# Schematic_v14.net
KiCad netlist of a schematic drawn in EAGLE
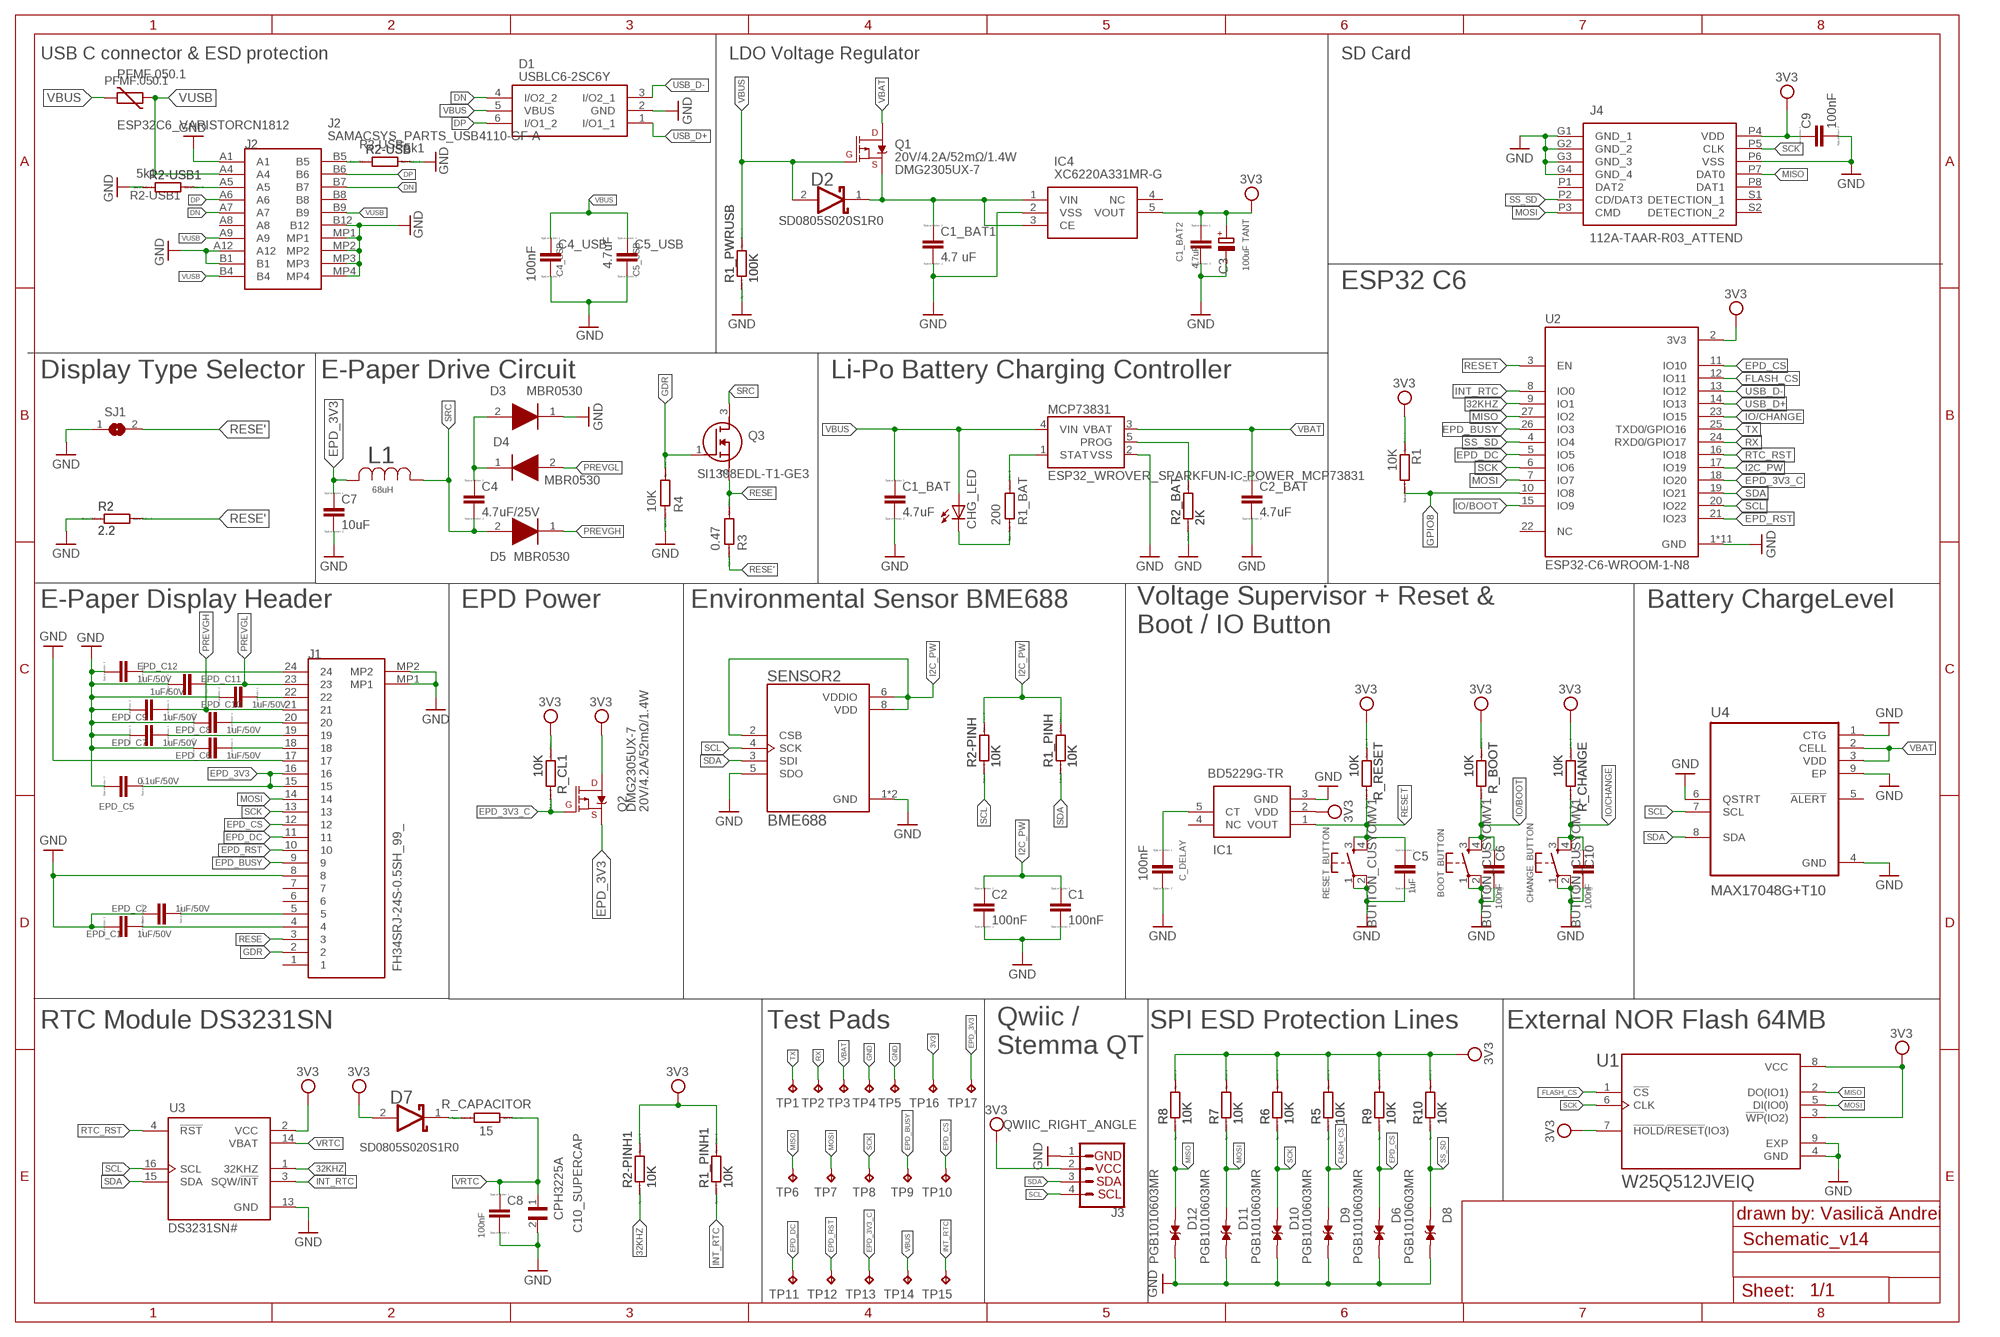
[diagram p0: schematic, sheet 1]

(export (version "E")
  (design (tool "Eeschema 10.0.6"))
  (components
    (comp (ref "BOOT_BUTTON")
      (value "BUTTON_CUSYOMV1")
      (footprint "eagle-import:MYBUTTON")
      (libsource (lib "eagle-import") (part "BUTTON_CUSYOMV1"))
    )
    (comp (ref "C1")
      (value "100nF")
      (footprint "eagle-import:ESP32_WROVER_EAGLE-LTSPICE_C0402")
      (libsource (lib "eagle-import") (part "ESP32_WROVER_EAGLE-LTSPICE_CC0402"))
    )
    (comp (ref "C1_BAT")
      (value "4.7uF")
      (footprint "eagle-import:ESP32_WROVER_EAGLE-LTSPICE_C0402")
      (libsource (lib "eagle-import") (part "ESP32_WROVER_EAGLE-LTSPICE_CC0402"))
    )
    (comp (ref "C1_BAT1")
      (value "4.7 uF")
      (footprint "eagle-import:EAGLE-LTSPICE_C0402")
      (fields (field (name "THERMALLOSS") "4.7 uF"))
      (libsource (lib "eagle-import") (part "EAGLE-LTSPICE_CC0402"))
    )
    (comp (ref "C1_BAT2")
      (value "4.7uF")
      (footprint "eagle-import:EAGLE-LTSPICE_C0402")
      (fields (field (name "SPICEPREFIX") "4.7uF"))
      (libsource (lib "eagle-import") (part "EAGLE-LTSPICE_CC0402"))
    )
    (comp (ref "C2")
      (value "100nF")
      (footprint "eagle-import:ESP32_WROVER_EAGLE-LTSPICE_C0402")
      (libsource (lib "eagle-import") (part "ESP32_WROVER_EAGLE-LTSPICE_CC0402"))
    )
    (comp (ref "C2_BAT")
      (value "4.7uF")
      (footprint "eagle-import:ESP32_WROVER_EAGLE-LTSPICE_C0402")
      (libsource (lib "eagle-import") (part "ESP32_WROVER_EAGLE-LTSPICE_CC0402"))
    )
    (comp (ref "C3")
      (value "100uF TANT")
      (footprint "eagle-import:RCL_CT3528")
      (fields (field (name "SPICEPREFIX") "100uF TANT"))
      (libsource (lib "eagle-import") (part "RCL_CPOL-EUCT3528"))
    )
    (comp (ref "C4")
      (value "4.7uF/25V")
      (footprint "eagle-import:ESP32_WROVER_EAGLE-LTSPICE_C0402")
      (libsource (lib "eagle-import") (part "ESP32_WROVER_EAGLE-LTSPICE_CC0402"))
    )
    (comp (ref "C4_USB")
      (value "100nF")
      (footprint "eagle-import:EAGLE-LTSPICE_C0402")
      (libsource (lib "eagle-import") (part "EAGLE-LTSPICE_CC0402"))
    )
    (comp (ref "C5")
      (value "1uF")
      (footprint "eagle-import:ESP32_WROVER_EAGLE-LTSPICE_C0402")
      (libsource (lib "eagle-import") (part "ESP32_WROVER_EAGLE-LTSPICE_CC0402"))
    )
    (comp (ref "C5_USB")
      (value "4.7uF")
      (footprint "eagle-import:EAGLE-LTSPICE_C0402")
      (libsource (lib "eagle-import") (part "EAGLE-LTSPICE_CC0402"))
    )
    (comp (ref "C6")
      (value "100nF")
      (footprint "eagle-import:ESP32_WROVER_EAGLE-LTSPICE_C0402")
      (libsource (lib "eagle-import") (part "ESP32_WROVER_EAGLE-LTSPICE_CC0402"))
    )
    (comp (ref "C7")
      (value "10uF")
      (footprint "eagle-import:ESP32_WROVER_EAGLE-LTSPICE_C0402")
      (libsource (lib "eagle-import") (part "ESP32_WROVER_EAGLE-LTSPICE_CC0402"))
    )
    (comp (ref "C8")
      (value "100nF")
      (footprint "eagle-import:ESP32_WROVER_EAGLE-LTSPICE_C0402")
      (libsource (lib "eagle-import") (part "ESP32_WROVER_EAGLE-LTSPICE_CC0402"))
    )
    (comp (ref "C9")
      (value "100nF")
      (footprint "eagle-import:EAGLE-LTSPICE_C0402")
      (fields (field (name "SPICEPREFIX") "100nF"))
      (libsource (lib "eagle-import") (part "EAGLE-LTSPICE_CC0402"))
    )
    (comp (ref "C10")
      (value "100nF")
      (footprint "eagle-import:ESP32_WROVER_EAGLE-LTSPICE_C0402")
      (libsource (lib "eagle-import") (part "ESP32_WROVER_EAGLE-LTSPICE_CC0402"))
    )
    (comp (ref "C10_SUPERCAP")
      (value "CPH3225A")
      (footprint "eagle-import:CAPCP3225X100N")
      (fields (field (name "MF") "Seiko Instruments"))
      (libsource (lib "eagle-import") (part "CPH3225A"))
    )
    (comp (ref "CHANGE_BUTTON")
      (value "BUTTON_CUSYOMV1")
      (footprint "eagle-import:MYBUTTON")
      (libsource (lib "eagle-import") (part "BUTTON_CUSYOMV1"))
    )
    (comp (ref "CHG_LED")
      (value "ADAFRUIT_LEDCHIP-LED0603")
      (footprint "eagle-import:ADAFRUIT_CHIP-LED0603")
      (libsource (lib "eagle-import") (part "ADAFRUIT_LEDCHIP-LED0603"))
    )
    (comp (ref "C_DELAY")
      (value "100nF")
      (footprint "eagle-import:ESP32_WROVER_EAGLE-LTSPICE_C0402")
      (libsource (lib "eagle-import") (part "ESP32_WROVER_EAGLE-LTSPICE_CC0402"))
    )
    (comp (ref "D1")
      (value "USBLC6-2SC6Y")
      (footprint "eagle-import:SOT95P280X145-6N")
      (fields (field (name "MF") "STMicroelectronics"))
      (libsource (lib "eagle-import") (part "USBLC6-2SC6Y"))
    )
    (comp (ref "D2")
      (value "ESP32_WROVER_AVX---SD0805S020S1R0_AVX_SD0805S020S1R0_0_0AVX_SD0805S020S1R0_0_0")
      (footprint "eagle-import:ESP32_WROVER_AVX---SD0805S020S1R0_AVX_SD0805S020S1R0_0")
      (fields
        (field (name "DIGIKEY_PART_NUMBER") "478-7800-1-ND")
        (field (name "MF") "AVX")
        (field (name "MOUSER_PART_NUMBER") "581-SD0805S020S1R0")
      )
      (libsource (lib "eagle-import") (part "ESP32_WROVER_AVX---SD0805S020S1R0_AVX_SD0805S020S1R0_0_0AVX_SD0805S020S1R0_0_0"))
    )
    (comp (ref "D3")
      (value "MBR0530")
      (footprint "eagle-import:SOD3716X135N")
      (fields (field (name "MF") "ON Semiconductor"))
      (libsource (lib "eagle-import") (part "MBR0530"))
    )
    (comp (ref "D4")
      (value "MBR0530")
      (footprint "eagle-import:SOD3716X135N")
      (fields (field (name "MF") "ON Semiconductor"))
      (libsource (lib "eagle-import") (part "MBR0530"))
    )
    (comp (ref "D5")
      (value "MBR0530")
      (footprint "eagle-import:SOD3716X135N")
      (fields (field (name "MF") "ON Semiconductor"))
      (libsource (lib "eagle-import") (part "MBR0530"))
    )
    (comp (ref "D6")
      (value "PGB1010603MR")
      (footprint "eagle-import:DIOC1608X36N")
      (fields (field (name "MF") "Littelfuse Inc."))
      (libsource (lib "eagle-import") (part "PGB1010603MR"))
    )
    (comp (ref "D7")
      (value "SD0805S020S1R0")
      (footprint "eagle-import:ESP32_WROVER_AVX---SD0805S020S1R0_AVX_SD0805S020S1R0_0")
      (fields
        (field (name "DIGIKEY_PART_NUMBER") "478-7800-1-ND")
        (field (name "MF") "AVX")
        (field (name "MOUSER_PART_NUMBER") "581-SD0805S020S1R0")
      )
      (libsource (lib "eagle-import") (part "ESP32_WROVER_AVX---SD0805S020S1R0_AVX_SD0805S020S1R0_0_0AVX_SD0805S020S1R0_0_0"))
    )
    (comp (ref "D8")
      (value "PGB1010603MR")
      (footprint "eagle-import:DIOC1608X36N")
      (fields (field (name "MF") "Littelfuse Inc."))
      (libsource (lib "eagle-import") (part "PGB1010603MR"))
    )
    (comp (ref "D9")
      (value "PGB1010603MR")
      (footprint "eagle-import:DIOC1608X36N")
      (fields (field (name "MF") "Littelfuse Inc."))
      (libsource (lib "eagle-import") (part "PGB1010603MR"))
    )
    (comp (ref "D10")
      (value "PGB1010603MR")
      (footprint "eagle-import:DIOC1608X36N")
      (fields (field (name "MF") "Littelfuse Inc."))
      (libsource (lib "eagle-import") (part "PGB1010603MR"))
    )
    (comp (ref "D11")
      (value "PGB1010603MR")
      (footprint "eagle-import:DIOC1608X36N")
      (fields (field (name "MF") "Littelfuse Inc."))
      (libsource (lib "eagle-import") (part "PGB1010603MR"))
    )
    (comp (ref "D12")
      (value "PGB1010603MR")
      (footprint "eagle-import:DIOC1608X36N")
      (fields (field (name "MF") "Littelfuse Inc."))
      (libsource (lib "eagle-import") (part "PGB1010603MR"))
    )
    (comp (ref "EPD_C1")
      (value "1uF/50V")
      (footprint "eagle-import:ESP32_WROVER_EAGLE-LTSPICE_C0402")
      (libsource (lib "eagle-import") (part "ESP32_WROVER_EAGLE-LTSPICE_CC0402"))
    )
    (comp (ref "EPD_C2")
      (value "1uF/50V")
      (footprint "eagle-import:ESP32_WROVER_EAGLE-LTSPICE_C0402")
      (libsource (lib "eagle-import") (part "ESP32_WROVER_EAGLE-LTSPICE_CC0402"))
    )
    (comp (ref "EPD_C5")
      (value "0.1uF/50V")
      (footprint "eagle-import:ESP32_WROVER_EAGLE-LTSPICE_C0402")
      (libsource (lib "eagle-import") (part "ESP32_WROVER_EAGLE-LTSPICE_CC0402"))
    )
    (comp (ref "EPD_C6")
      (value "1uF/50V")
      (footprint "eagle-import:ESP32_WROVER_EAGLE-LTSPICE_C0402")
      (libsource (lib "eagle-import") (part "ESP32_WROVER_EAGLE-LTSPICE_CC0402"))
    )
    (comp (ref "EPD_C7")
      (value "1uF/50V")
      (footprint "eagle-import:ESP32_WROVER_EAGLE-LTSPICE_C0402")
      (libsource (lib "eagle-import") (part "ESP32_WROVER_EAGLE-LTSPICE_CC0402"))
    )
    (comp (ref "EPD_C8")
      (value "1uF/50V")
      (footprint "eagle-import:ESP32_WROVER_EAGLE-LTSPICE_C0402")
      (libsource (lib "eagle-import") (part "ESP32_WROVER_EAGLE-LTSPICE_CC0402"))
    )
    (comp (ref "EPD_C9")
      (value "1uF/50V")
      (footprint "eagle-import:ESP32_WROVER_EAGLE-LTSPICE_C0402")
      (libsource (lib "eagle-import") (part "ESP32_WROVER_EAGLE-LTSPICE_CC0402"))
    )
    (comp (ref "EPD_C10")
      (value "1uF/50V")
      (footprint "eagle-import:ESP32_WROVER_EAGLE-LTSPICE_C0402")
      (libsource (lib "eagle-import") (part "ESP32_WROVER_EAGLE-LTSPICE_CC0402"))
    )
    (comp (ref "EPD_C11")
      (value "1uF/50V")
      (footprint "eagle-import:ESP32_WROVER_EAGLE-LTSPICE_C0402")
      (libsource (lib "eagle-import") (part "ESP32_WROVER_EAGLE-LTSPICE_CC0402"))
    )
    (comp (ref "EPD_C12")
      (value "1uF/50V")
      (footprint "eagle-import:ESP32_WROVER_EAGLE-LTSPICE_C0402")
      (libsource (lib "eagle-import") (part "ESP32_WROVER_EAGLE-LTSPICE_CC0402"))
    )
    (comp (ref "IC1")
      (value "BD5229G-TR")
      (footprint "eagle-import:SOT95P280X125-5N")
      (fields (field (name "MOUSER_PART_NUMBER") "755-BD5229G-TR"))
      (libsource (lib "eagle-import") (part "BD5229G-TR"))
    )
    (comp (ref "IC4")
      (value "XC6220A331MR-G")
      (footprint "eagle-import:SOT95P280X120-5N")
      (fields (field (name "MOUSER_PART_NUMBER") "865-XC6220A331MR-G"))
      (libsource (lib "eagle-import") (part "XC6220A331MR-G"))
    )
    (comp (ref "J1")
      (value "FH34SRJ-24S-0.5SH_99_")
      (footprint "eagle-import:FH34SRJ24S05SH99")
      (fields
        (field (name "MANUFACTURER_PART_NUMBER") "FH34SRJ-24S-0.5SH(99)")
        (field (name "MOUSER_PART_NUMBER") "798-FH34SRJ24S05SH99")
      )
      (libsource (lib "eagle-import") (part "FH34SRJ-24S-0.5SH_99_"))
    )
    (comp (ref "J2")
      (value "SAMACSYS_PARTS_USB4110-GF-A")
      (footprint "eagle-import:SAMACSYS_PARTS_USB4110GFA")
      (fields
        (field (name "MANUFACTURER_PART_NUMBER") "USB4110-GF-A")
        (field (name "MOUSER_PART_NUMBER") "640-USB4110-GF-A")
      )
      (libsource (lib "eagle-import") (part "SAMACSYS_PARTS_USB4110-GF-A"))
    )
    (comp (ref "J3")
      (value "QWIIC_RIGHT_ANGLE")
      (footprint "eagle-import:JST04_1MM_RA")
      (libsource (lib "eagle-import") (part "QWIIC_CONNECTORJS-1MM"))
    )
    (comp (ref "J4")
      (value "112A-TAAR-R03_ATTEND")
      (footprint "eagle-import:112ATAARR03ATTEND")
      (fields (field (name "MANUFACTURER_PART_NUMBER") "112A-TAAR-R03 ATTEND"))
      (libsource (lib "eagle-import") (part "112A-TAAR-R03_ATTEND"))
    )
    (comp (ref "L1")
      (value "744043680IND_4828-WE-TPC_WRE")
      (footprint "eagle-import:IND_4828-WE-TPC_WRE")
      (fields
        (field (name "MANUFACTURER_PART_NUMBER") "744043680")
        (field (name "MANUFACTURER_PART_NUMBER_1") "68uH")
        (field (name "COPYRIGHT") "Copyright (C) 2024 Ultra Librarian. All rights reserved.")
      )
      (libsource (lib "eagle-import") (part "744043680IND_4828-WE-TPC_WRE"))
    )
    (comp (ref "MCP73831")
      (value "ESP32_WROVER_SPARKFUN-IC-POWER_MCP73831")
      (footprint "eagle-import:ESP32_WROVER_SPARKFUN-IC-POWER_SOT23-5")
      (libsource (lib "eagle-import") (part "ESP32_WROVER_SPARKFUN-IC-POWER_MCP73831"))
    )
    (comp (ref "PFMF.050.1")
      (value "ESP32C6_VARISTORCN1812")
      (footprint "eagle-import:ESP32C6_VARISTOR_CT_CN1812")
      (libsource (lib "eagle-import") (part "ESP32C6_VARISTORCN1812"))
    )
    (comp (ref "Q1")
      (value "20V/4.2A/52mΩ/1.4W")
      (footprint "eagle-import:ESP32_WROVER_SPARKFUN-DISCRETESEMI_SOT23-3")
      (libsource (lib "eagle-import") (part "ESP32_WROVER_SPARKFUN-DISCRETESEMI_MOSFET_PCH-DMG2305UX-7"))
    )
    (comp (ref "Q2")
      (value "20V/4.2A/52mΩ/1.4W")
      (footprint "eagle-import:ESP32_WROVER_SPARKFUN-DISCRETESEMI_SOT23-3")
      (libsource (lib "eagle-import") (part "ESP32_WROVER_SPARKFUN-DISCRETESEMI_MOSFET_PCH-DMG2305UX-7"))
    )
    (comp (ref "Q3")
      (value "SI1308EDL-T1-GE3")
      (footprint "eagle-import:SOT65P210X110-3N")
      (fields (field (name "MF") "Vishay Siliconix"))
      (libsource (lib "eagle-import") (part "SI1308EDL-T1-GE3"))
    )
    (comp (ref "R1")
      (value "10K")
      (footprint "eagle-import:ESP32_WROVER_EAGLE-LTSPICE_R0402")
      (libsource (lib "eagle-import") (part "ESP32_WROVER_EAGLE-LTSPICE_RR0402"))
    )
    (comp (ref "R1_BAT")
      (value "200")
      (footprint "eagle-import:ESP32_WROVER_EAGLE-LTSPICE_R0402")
      (libsource (lib "eagle-import") (part "ESP32_WROVER_EAGLE-LTSPICE_RR0402"))
    )
    (comp (ref "R1_PINH")
      (value "10K")
      (footprint "eagle-import:ESP32_WROVER_EAGLE-LTSPICE_R0402")
      (libsource (lib "eagle-import") (part "ESP32_WROVER_EAGLE-LTSPICE_RR0402"))
    )
    (comp (ref "R1_PINH1")
      (value "10K")
      (footprint "eagle-import:ESP32_WROVER_EAGLE-LTSPICE_R0402")
      (libsource (lib "eagle-import") (part "ESP32_WROVER_EAGLE-LTSPICE_RR0402"))
    )
    (comp (ref "R1_PWRUSB")
      (value "100K")
      (footprint "eagle-import:ESP32_WROVER_EAGLE-LTSPICE_R0402")
      (fields (field (name "SPICEMODEL") "100K"))
      (libsource (lib "eagle-import") (part "ESP32_WROVER_EAGLE-LTSPICE_RR0402"))
    )
    (comp (ref "R2")
      (value "2.2")
      (footprint "eagle-import:ESP32_WROVER_EAGLE-LTSPICE_R0402")
      (fields (field (name "SPICEMODEL") "2.2"))
      (libsource (lib "eagle-import") (part "ESP32_WROVER_EAGLE-LTSPICE_RR0402"))
    )
    (comp (ref "R2-PINH")
      (value "10K")
      (footprint "eagle-import:ESP32_WROVER_EAGLE-LTSPICE_R0402")
      (libsource (lib "eagle-import") (part "ESP32_WROVER_EAGLE-LTSPICE_RR0402"))
    )
    (comp (ref "R2-PINH1")
      (value "10K")
      (footprint "eagle-import:ESP32_WROVER_EAGLE-LTSPICE_R0402")
      (libsource (lib "eagle-import") (part "ESP32_WROVER_EAGLE-LTSPICE_RR0402"))
    )
    (comp (ref "R2-USB")
      (value "5k1")
      (footprint "eagle-import:ESP32_WROVER_EAGLE-LTSPICE_R0402")
      (libsource (lib "eagle-import") (part "ESP32_WROVER_EAGLE-LTSPICE_RR0402"))
    )
    (comp (ref "R2-USB1")
      (value "5k1")
      (footprint "eagle-import:ESP32_WROVER_EAGLE-LTSPICE_R0402")
      (libsource (lib "eagle-import") (part "ESP32_WROVER_EAGLE-LTSPICE_RR0402"))
    )
    (comp (ref "R2_BAT")
      (value "2K")
      (footprint "eagle-import:ESP32_WROVER_EAGLE-LTSPICE_R0402")
      (libsource (lib "eagle-import") (part "ESP32_WROVER_EAGLE-LTSPICE_RR0402"))
    )
    (comp (ref "R3")
      (value "0.47")
      (footprint "eagle-import:ESP32_WROVER_EAGLE-LTSPICE_R0402")
      (libsource (lib "eagle-import") (part "ESP32_WROVER_EAGLE-LTSPICE_RR0402"))
    )
    (comp (ref "R4")
      (value "10K")
      (footprint "eagle-import:ESP32_WROVER_EAGLE-LTSPICE_R0402")
      (libsource (lib "eagle-import") (part "ESP32_WROVER_EAGLE-LTSPICE_RR0402"))
    )
    (comp (ref "R5")
      (value "10K")
      (footprint "eagle-import:ESP32_WROVER_EAGLE-LTSPICE_R0402")
      (libsource (lib "eagle-import") (part "ESP32_WROVER_EAGLE-LTSPICE_RR0402"))
    )
    (comp (ref "R6")
      (value "10K")
      (footprint "eagle-import:ESP32_WROVER_EAGLE-LTSPICE_R0402")
      (libsource (lib "eagle-import") (part "ESP32_WROVER_EAGLE-LTSPICE_RR0402"))
    )
    (comp (ref "R7")
      (value "10K")
      (footprint "eagle-import:ESP32_WROVER_EAGLE-LTSPICE_R0402")
      (libsource (lib "eagle-import") (part "ESP32_WROVER_EAGLE-LTSPICE_RR0402"))
    )
    (comp (ref "R8")
      (value "10K")
      (footprint "eagle-import:ESP32_WROVER_EAGLE-LTSPICE_R0402")
      (libsource (lib "eagle-import") (part "ESP32_WROVER_EAGLE-LTSPICE_RR0402"))
    )
    (comp (ref "R9")
      (value "10K")
      (footprint "eagle-import:ESP32_WROVER_EAGLE-LTSPICE_R0402")
      (libsource (lib "eagle-import") (part "ESP32_WROVER_EAGLE-LTSPICE_RR0402"))
    )
    (comp (ref "R10")
      (value "10K")
      (footprint "eagle-import:ESP32_WROVER_EAGLE-LTSPICE_R0402")
      (libsource (lib "eagle-import") (part "ESP32_WROVER_EAGLE-LTSPICE_RR0402"))
    )
    (comp (ref "RESET_BUTTON")
      (value "BUTTON_CUSYOMV1")
      (footprint "eagle-import:MYBUTTON")
      (libsource (lib "eagle-import") (part "BUTTON_CUSYOMV1"))
    )
    (comp (ref "R_BOOT")
      (value "10K")
      (footprint "eagle-import:ESP32_WROVER_EAGLE-LTSPICE_R0402")
      (libsource (lib "eagle-import") (part "ESP32_WROVER_EAGLE-LTSPICE_RR0402"))
    )
    (comp (ref "R_CAPACITOR")
      (value "15")
      (footprint "eagle-import:ESP32_WROVER_EAGLE-LTSPICE_R0402")
      (libsource (lib "eagle-import") (part "ESP32_WROVER_EAGLE-LTSPICE_RR0402"))
    )
    (comp (ref "R_CHANGE")
      (value "10K")
      (footprint "eagle-import:ESP32_WROVER_EAGLE-LTSPICE_R0402")
      (libsource (lib "eagle-import") (part "ESP32_WROVER_EAGLE-LTSPICE_RR0402"))
    )
    (comp (ref "R_CL1")
      (value "10K")
      (footprint "eagle-import:ESP32_WROVER_EAGLE-LTSPICE_R0402")
      (libsource (lib "eagle-import") (part "ESP32_WROVER_EAGLE-LTSPICE_RR0402"))
    )
    (comp (ref "R_RESET")
      (value "10K")
      (footprint "eagle-import:ESP32_WROVER_EAGLE-LTSPICE_R0402")
      (libsource (lib "eagle-import") (part "ESP32_WROVER_EAGLE-LTSPICE_RR0402"))
    )
    (comp (ref "SENSOR2")
      (value "BME688")
      (footprint "eagle-import:ESP32_WROVER_BME680_PSON80P300X300X100-8N")
      (fields (field (name "MF") "Bosch Sensortec") (field (name "MP") "BME680"))
      (libsource (lib "eagle-import") (part "ESP32_WROVER_BME680_BME680"))
    )
    (comp (ref "SJ1") (value "SJ") (footprint "eagle-import:SJ") (libsource (lib "eagle-import") (part "SJ")))
    (comp (ref "TP1")
      (value "TPTP20R")
      (footprint "eagle-import:TP20R")
      (libsource (lib "eagle-import") (part "TPTP20R"))
    )
    (comp (ref "TP2")
      (value "TPTP20R")
      (footprint "eagle-import:TP20R")
      (libsource (lib "eagle-import") (part "TPTP20R"))
    )
    (comp (ref "TP3")
      (value "TPTP20R")
      (footprint "eagle-import:TP20R")
      (libsource (lib "eagle-import") (part "TPTP20R"))
    )
    (comp (ref "TP4")
      (value "TPTP20R")
      (footprint "eagle-import:TP20R")
      (libsource (lib "eagle-import") (part "TPTP20R"))
    )
    (comp (ref "TP5")
      (value "TPTP20R")
      (footprint "eagle-import:TP20R")
      (libsource (lib "eagle-import") (part "TPTP20R"))
    )
    (comp (ref "TP6")
      (value "TPTP20R")
      (footprint "eagle-import:TP20R")
      (libsource (lib "eagle-import") (part "TPTP20R"))
    )
    (comp (ref "TP7")
      (value "TPTP20R")
      (footprint "eagle-import:TP20R")
      (libsource (lib "eagle-import") (part "TPTP20R"))
    )
    (comp (ref "TP8")
      (value "TPTP20R")
      (footprint "eagle-import:TP20R")
      (libsource (lib "eagle-import") (part "TPTP20R"))
    )
    (comp (ref "TP9")
      (value "TPTP20R")
      (footprint "eagle-import:TP20R")
      (libsource (lib "eagle-import") (part "TPTP20R"))
    )
    (comp (ref "TP10")
      (value "TPTP20R")
      (footprint "eagle-import:TP20R")
      (libsource (lib "eagle-import") (part "TPTP20R"))
    )
    (comp (ref "TP11")
      (value "TPTP20R")
      (footprint "eagle-import:TP20R")
      (libsource (lib "eagle-import") (part "TPTP20R"))
    )
    (comp (ref "TP12")
      (value "TPTP20R")
      (footprint "eagle-import:TP20R")
      (libsource (lib "eagle-import") (part "TPTP20R"))
    )
    (comp (ref "TP13")
      (value "TPTP20R")
      (footprint "eagle-import:TP20R")
      (libsource (lib "eagle-import") (part "TPTP20R"))
    )
    (comp (ref "TP14")
      (value "TPTP20R")
      (footprint "eagle-import:TP20R")
      (libsource (lib "eagle-import") (part "TPTP20R"))
    )
    (comp (ref "TP15")
      (value "TPTP20R")
      (footprint "eagle-import:TP20R")
      (libsource (lib "eagle-import") (part "TPTP20R"))
    )
    (comp (ref "TP16")
      (value "TPTP20R")
      (footprint "eagle-import:TP20R")
      (libsource (lib "eagle-import") (part "TPTP20R"))
    )
    (comp (ref "TP17")
      (value "TPTP20R")
      (footprint "eagle-import:TP20R")
      (libsource (lib "eagle-import") (part "TPTP20R"))
    )
    (comp (ref "U1")
      (value "W25Q512JVEIQ")
      (footprint "eagle-import:SON127P600X800X80-9N")
      (fields (field (name "MF") "Winbond Electronics"))
      (libsource (lib "eagle-import") (part "W25Q512JVEIQ"))
    )
    (comp (ref "U2")
      (value "ESP32-C6-WROOM-1-N8")
      (footprint "eagle-import:XCVR_ESP32-C6-WROOM-1-N8")
      (fields (field (name "MF") "Espressif Systems"))
      (libsource (lib "eagle-import") (part "ESP32-C6-WROOM-1-N8"))
    )
    (comp (ref "U3")
      (value "DS3231SN#")
      (footprint "eagle-import:SOIC127P1032X265-16N")
      (fields (field (name "MF") "Analog Devices"))
      (libsource (lib "eagle-import") (part "DS3231SN#"))
    )
    (comp (ref "U4")
      (value "MAX17048G+T10")
      (footprint "eagle-import:SON50P200X200X80-9N")
      (fields (field (name "MF") "Analog Devices"))
      (libsource (lib "eagle-import") (part "MAX17048G+T10"))
    )
  )
  (nets
    (net (code "1") (name "3V3") (class "Default")
      (node (ref "C1_BAT2") (pin "1") (pinfunction "1_1") (pintype "passive"))
      (node (ref "C3") (pin "+") (pinfunction "+_+") (pintype "passive"))
      (node (ref "C9") (pin "1") (pinfunction "1_1") (pintype "passive"))
      (node (ref "D7") (pin "2") (pinfunction "ANODE_2") (pintype "bidirectional"))
      (node (ref "IC1") (pin "2") (pinfunction "VDD_2") (pintype "bidirectional"))
      (node (ref "IC4") (pin "5") (pinfunction "VOUT_5") (pintype "bidirectional"))
      (node (ref "J3") (pin "2") (pinfunction "2_2") (pintype "power_in"))
      (node (ref "J4") (pin "P4") (pinfunction "VDD_P4") (pintype "bidirectional"))
      (node (ref "Q2") (pin "3") (pinfunction "D_3") (pintype "bidirectional"))
      (node (ref "R1") (pin "1") (pinfunction "1_1") (pintype "passive"))
      (node (ref "R10") (pin "2") (pinfunction "2_2") (pintype "passive"))
      (node (ref "R1_PINH1") (pin "2") (pinfunction "2_2") (pintype "passive"))
      (node (ref "R2-PINH1") (pin "2") (pinfunction "2_2") (pintype "passive"))
      (node (ref "R5") (pin "2") (pinfunction "2_2") (pintype "passive"))
      (node (ref "R6") (pin "2") (pinfunction "2_2") (pintype "passive"))
      (node (ref "R7") (pin "2") (pinfunction "2_2") (pintype "passive"))
      (node (ref "R8") (pin "2") (pinfunction "2_2") (pintype "passive"))
      (node (ref "R9") (pin "2") (pinfunction "2_2") (pintype "passive"))
      (node (ref "R_BOOT") (pin "1") (pinfunction "1_1") (pintype "passive"))
      (node (ref "R_CHANGE") (pin "1") (pinfunction "1_1") (pintype "passive"))
      (node (ref "R_CL1") (pin "1") (pinfunction "1_1") (pintype "passive"))
      (node (ref "R_RESET") (pin "1") (pinfunction "1_1") (pintype "passive"))
      (node (ref "TP16") (pin "TP") (pinfunction "TP_TP") (pintype "input"))
      (node (ref "U1") (pin "3") (pinfunction "~{WP}(IO2)_3") (pintype "bidirectional"))
      (node (ref "U1") (pin "7") (pinfunction "~{HOLD}/~{RESET}(IO3)_7") (pintype "bidirectional"))
      (node (ref "U1") (pin "8") (pinfunction "VCC_8") (pintype "power_in"))
      (node (ref "U2") (pin "2") (pinfunction "3V3_2") (pintype "power_in"))
      (node (ref "U3") (pin "2") (pinfunction "VCC_2") (pintype "power_in"))
    )
    (net (code "2") (name "32KHZ") (class "Default")
      (node (ref "R2-PINH1") (pin "1") (pinfunction "1_1") (pintype "passive"))
      (node (ref "U2") (pin "9") (pinfunction "IO1_9") (pintype "bidirectional"))
      (node (ref "U3") (pin "1") (pinfunction "32KHZ_1") (pintype "output"))
    )
    (net (code "3") (name "DN") (class "Default")
      (node (ref "D1") (pin "4") (pinfunction "I/O2_2_4") (pintype "bidirectional"))
      (node (ref "J2") (pin "A7") (pinfunction "A7_A7") (pintype "bidirectional"))
      (node (ref "J2") (pin "B7") (pinfunction "B7_B7") (pintype "bidirectional"))
    )
    (net (code "4") (name "DP") (class "Default")
      (node (ref "D1") (pin "6") (pinfunction "I/O1_2_6") (pintype "bidirectional"))
      (node (ref "J2") (pin "A6") (pinfunction "A6_A6") (pintype "bidirectional"))
      (node (ref "J2") (pin "B6") (pinfunction "B6_B6") (pintype "bidirectional"))
    )
    (net (code "5") (name "EPD_3V3") (class "Default")
      (node (ref "C7") (pin "1") (pinfunction "1_1") (pintype "passive"))
      (node (ref "EPD_C5") (pin "1") (pinfunction "1_1") (pintype "passive"))
      (node (ref "J1") (pin "15") (pinfunction "15_15") (pintype "bidirectional"))
      (node (ref "J1") (pin "16") (pinfunction "16_16") (pintype "bidirectional"))
      (node (ref "L1") (pin "2") (pinfunction "2_2") (pintype "passive"))
      (node (ref "Q2") (pin "2") (pinfunction "S_2") (pintype "bidirectional"))
      (node (ref "TP17") (pin "TP") (pinfunction "TP_TP") (pintype "input"))
    )
    (net (code "6") (name "EPD_3V3_C") (class "Default")
      (node (ref "Q2") (pin "1") (pinfunction "G_1") (pintype "bidirectional"))
      (node (ref "R_CL1") (pin "2") (pinfunction "2_2") (pintype "passive"))
      (node (ref "TP13") (pin "TP") (pinfunction "TP_TP") (pintype "input"))
      (node (ref "U2") (pin "18") (pinfunction "IO20_18") (pintype "bidirectional"))
    )
    (net (code "7") (name "EPD_BUSY") (class "Default")
      (node (ref "J1") (pin "9") (pinfunction "9_9") (pintype "bidirectional"))
      (node (ref "TP9") (pin "TP") (pinfunction "TP_TP") (pintype "input"))
      (node (ref "U2") (pin "26") (pinfunction "IO3_26") (pintype "bidirectional"))
    )
    (net (code "8") (name "EPD_CS") (class "Default")
      (node (ref "D6") (pin "1") (pinfunction "1_1") (pintype "passive"))
      (node (ref "J1") (pin "12") (pinfunction "12_12") (pintype "bidirectional"))
      (node (ref "R9") (pin "1") (pinfunction "1_1") (pintype "passive"))
      (node (ref "TP10") (pin "TP") (pinfunction "TP_TP") (pintype "input"))
      (node (ref "U2") (pin "11") (pinfunction "IO10_11") (pintype "bidirectional"))
    )
    (net (code "9") (name "EPD_DC") (class "Default")
      (node (ref "J1") (pin "11") (pinfunction "11_11") (pintype "bidirectional"))
      (node (ref "TP11") (pin "TP") (pinfunction "TP_TP") (pintype "input"))
      (node (ref "U2") (pin "5") (pinfunction "IO5_5") (pintype "bidirectional"))
    )
    (net (code "10") (name "EPD_RST") (class "Default")
      (node (ref "J1") (pin "10") (pinfunction "10_10") (pintype "bidirectional"))
      (node (ref "TP12") (pin "TP") (pinfunction "TP_TP") (pintype "input"))
      (node (ref "U2") (pin "21") (pinfunction "IO23_21") (pintype "bidirectional"))
    )
    (net (code "11") (name "FLASH_CS") (class "Default")
      (node (ref "D9") (pin "1") (pinfunction "1_1") (pintype "passive"))
      (node (ref "R5") (pin "1") (pinfunction "1_1") (pintype "passive"))
      (node (ref "U1") (pin "1") (pinfunction "~{CS}_1") (pintype "input"))
      (node (ref "U2") (pin "12") (pinfunction "IO11_12") (pintype "bidirectional"))
    )
    (net (code "12") (name "GDR") (class "Default")
      (node (ref "J1") (pin "2") (pinfunction "2_2") (pintype "bidirectional"))
      (node (ref "Q3") (pin "1") (pinfunction "G_1") (pintype "bidirectional"))
      (node (ref "R4") (pin "2") (pinfunction "2_2") (pintype "passive"))
    )
    (net (code "13") (name "GND") (class "Default")
      (node (ref "BOOT_BUTTON") (pin "1") (pinfunction "1_1") (pintype "passive"))
      (node (ref "BOOT_BUTTON") (pin "2") (pinfunction "2_2") (pintype "passive"))
      (node (ref "C1") (pin "2") (pinfunction "2_2") (pintype "passive"))
      (node (ref "C10") (pin "1") (pinfunction "1_1") (pintype "passive"))
      (node (ref "C10_SUPERCAP") (pin "2") (pinfunction "2_2") (pintype "passive"))
      (node (ref "C1_BAT") (pin "2") (pinfunction "2_2") (pintype "passive"))
      (node (ref "C1_BAT1") (pin "2") (pinfunction "2_2") (pintype "passive"))
      (node (ref "C1_BAT2") (pin "2") (pinfunction "2_2") (pintype "passive"))
      (node (ref "C2") (pin "2") (pinfunction "2_2") (pintype "passive"))
      (node (ref "C2_BAT") (pin "2") (pinfunction "2_2") (pintype "passive"))
      (node (ref "C3") (pin "-") (pinfunction "-_-") (pintype "passive"))
      (node (ref "C4_USB") (pin "2") (pinfunction "2_2") (pintype "passive"))
      (node (ref "C5") (pin "2") (pinfunction "2_2") (pintype "passive"))
      (node (ref "C5_USB") (pin "2") (pinfunction "2_2") (pintype "passive"))
      (node (ref "C6") (pin "1") (pinfunction "1_1") (pintype "passive"))
      (node (ref "C7") (pin "2") (pinfunction "2_2") (pintype "passive"))
      (node (ref "C8") (pin "2") (pinfunction "2_2") (pintype "passive"))
      (node (ref "C9") (pin "2") (pinfunction "2_2") (pintype "passive"))
      (node (ref "CHANGE_BUTTON") (pin "1") (pinfunction "1_1") (pintype "passive"))
      (node (ref "CHANGE_BUTTON") (pin "2") (pinfunction "2_2") (pintype "passive"))
      (node (ref "C_DELAY") (pin "2") (pinfunction "2_2") (pintype "passive"))
      (node (ref "D1") (pin "2") (pinfunction "GND_2") (pintype "bidirectional"))
      (node (ref "D10") (pin "2") (pinfunction "2_2") (pintype "passive"))
      (node (ref "D11") (pin "2") (pinfunction "2_2") (pintype "passive"))
      (node (ref "D12") (pin "2") (pinfunction "2_2") (pintype "passive"))
      (node (ref "D3") (pin "1") (pinfunction "K_1") (pintype "bidirectional"))
      (node (ref "D6") (pin "2") (pinfunction "2_2") (pintype "passive"))
      (node (ref "D8") (pin "2") (pinfunction "2_2") (pintype "passive"))
      (node (ref "D9") (pin "2") (pinfunction "2_2") (pintype "passive"))
      (node (ref "EPD_C1") (pin "2") (pinfunction "2_2") (pintype "passive"))
      (node (ref "EPD_C10") (pin "2") (pinfunction "2_2") (pintype "passive"))
      (node (ref "EPD_C11") (pin "2") (pinfunction "2_2") (pintype "passive"))
      (node (ref "EPD_C12") (pin "2") (pinfunction "2_2") (pintype "passive"))
      (node (ref "EPD_C2") (pin "2") (pinfunction "2_2") (pintype "passive"))
      (node (ref "EPD_C5") (pin "2") (pinfunction "2_2") (pintype "passive"))
      (node (ref "EPD_C6") (pin "2") (pinfunction "2_2") (pintype "passive"))
      (node (ref "EPD_C7") (pin "2") (pinfunction "2_2") (pintype "passive"))
      (node (ref "EPD_C8") (pin "2") (pinfunction "2_2") (pintype "passive"))
      (node (ref "EPD_C9") (pin "2") (pinfunction "2_2") (pintype "passive"))
      (node (ref "IC1") (pin "3") (pinfunction "GND_3") (pintype "bidirectional"))
      (node (ref "IC4") (pin "2") (pinfunction "VSS_2") (pintype "bidirectional"))
      (node (ref "J1") (pin "17") (pinfunction "17_17") (pintype "bidirectional"))
      (node (ref "J1") (pin "8") (pinfunction "8_8") (pintype "bidirectional"))
      (node (ref "J1") (pin "MP1") (pinfunction "MP1_MP1") (pintype "bidirectional"))
      (node (ref "J1") (pin "MP2") (pinfunction "MP2_MP2") (pintype "bidirectional"))
      (node (ref "J2") (pin "A1") (pinfunction "A1_A1") (pintype "bidirectional"))
      (node (ref "J2") (pin "A12") (pinfunction "A12_A12") (pintype "bidirectional"))
      (node (ref "J2") (pin "B1") (pinfunction "B1_B1") (pintype "bidirectional"))
      (node (ref "J2") (pin "B12") (pinfunction "B12_B12") (pintype "bidirectional"))
      (node (ref "J2") (pin "MP1") (pinfunction "MP1_MP1") (pintype "bidirectional"))
      (node (ref "J2") (pin "MP2") (pinfunction "MP2_MP2") (pintype "bidirectional"))
      (node (ref "J2") (pin "MP3") (pinfunction "MP3_MP3") (pintype "bidirectional"))
      (node (ref "J2") (pin "MP4") (pinfunction "MP4_MP4") (pintype "bidirectional"))
      (node (ref "J3") (pin "1") (pinfunction "1_1") (pintype "power_in"))
      (node (ref "J4") (pin "G1") (pinfunction "GND_1_G1") (pintype "bidirectional"))
      (node (ref "J4") (pin "G2") (pinfunction "GND_2_G2") (pintype "bidirectional"))
      (node (ref "J4") (pin "G3") (pinfunction "GND_3_G3") (pintype "bidirectional"))
      (node (ref "J4") (pin "G4") (pinfunction "GND_4_G4") (pintype "bidirectional"))
      (node (ref "J4") (pin "P6") (pinfunction "VSS_P6") (pintype "bidirectional"))
      (node (ref "MCP73831") (pin "2") (pinfunction "VSS_2") (pintype "power_in"))
      (node (ref "R1_PWRUSB") (pin "1") (pinfunction "1_1") (pintype "passive"))
      (node (ref "R2") (pin "1") (pinfunction "1_1") (pintype "passive"))
      (node (ref "R2-USB") (pin "2") (pinfunction "2_2") (pintype "passive"))
      (node (ref "R2-USB1") (pin "1") (pinfunction "1_1") (pintype "passive"))
      (node (ref "R2_BAT") (pin "1") (pinfunction "1_1") (pintype "passive"))
      (node (ref "R4") (pin "1") (pinfunction "1_1") (pintype "passive"))
      (node (ref "RESET_BUTTON") (pin "1") (pinfunction "1_1") (pintype "passive"))
      (node (ref "RESET_BUTTON") (pin "2") (pinfunction "2_2") (pintype "passive"))
      (node (ref "SENSOR2") (pin "1") (pinfunction "GND_1") (pintype "power_in"))
      (node (ref "SENSOR2") (pin "5") (pinfunction "SDO_5") (pintype "bidirectional"))
      (node (ref "SENSOR2") (pin "7") (pinfunction "GND_7") (pintype "power_in"))
      (node (ref "SJ1") (pin "1") (pinfunction "1_1") (pintype "passive"))
      (node (ref "TP4") (pin "TP") (pinfunction "TP_TP") (pintype "input"))
      (node (ref "TP5") (pin "TP") (pinfunction "TP_TP") (pintype "input"))
      (node (ref "U1") (pin "4") (pinfunction "GND_4") (pintype "power_in"))
      (node (ref "U1") (pin "9") (pinfunction "EXP_9") (pintype "passive"))
      (node (ref "U2") (pin "1") (pinfunction "GND_1") (pintype "power_in"))
      (node (ref "U2") (pin "28") (pinfunction "GND_28") (pintype "power_in"))
      (node (ref "U2") (pin "29_1") (pinfunction "GND_29_1") (pintype "power_in"))
      (node (ref "U2") (pin "29_2") (pinfunction "GND_29_2") (pintype "power_in"))
      (node (ref "U2") (pin "29_3") (pinfunction "GND_29_3") (pintype "power_in"))
      (node (ref "U2") (pin "29_4") (pinfunction "GND_29_4") (pintype "power_in"))
      (node (ref "U2") (pin "29_5") (pinfunction "GND_29_5") (pintype "power_in"))
      (node (ref "U2") (pin "29_6") (pinfunction "GND_29_6") (pintype "power_in"))
      (node (ref "U2") (pin "29_7") (pinfunction "GND_29_7") (pintype "power_in"))
      (node (ref "U2") (pin "29_8") (pinfunction "GND_29_8") (pintype "power_in"))
      (node (ref "U2") (pin "29_9") (pinfunction "GND_29_9") (pintype "power_in"))
      (node (ref "U3") (pin "13") (pinfunction "GND_13") (pintype "power_in"))
      (node (ref "U4") (pin "1") (pinfunction "CTG_1") (pintype "power_in"))
      (node (ref "U4") (pin "4") (pinfunction "GND_4") (pintype "power_in"))
      (node (ref "U4") (pin "6") (pinfunction "QSTRT_6") (pintype "input"))
      (node (ref "U4") (pin "9") (pinfunction "EP_9") (pintype "power_in"))
    )
    (net (code "14") (name "GPIO8") (class "Default")
      (node (ref "R1") (pin "2") (pinfunction "2_2") (pintype "passive"))
      (node (ref "U2") (pin "10") (pinfunction "IO8_10") (pintype "bidirectional"))
    )
    (net (code "15") (name "I2C_PW") (class "Default")
      (node (ref "C1") (pin "1") (pinfunction "1_1") (pintype "passive"))
      (node (ref "C2") (pin "1") (pinfunction "1_1") (pintype "passive"))
      (node (ref "R1_PINH") (pin "2") (pinfunction "2_2") (pintype "passive"))
      (node (ref "R2-PINH") (pin "2") (pinfunction "2_2") (pintype "passive"))
      (node (ref "SENSOR2") (pin "2") (pinfunction "CSB_2") (pintype "input"))
      (node (ref "SENSOR2") (pin "6") (pinfunction "VDDIO_6") (pintype "power_in"))
      (node (ref "SENSOR2") (pin "8") (pinfunction "VDD_8") (pintype "power_in"))
      (node (ref "U2") (pin "17") (pinfunction "IO19_17") (pintype "bidirectional"))
    )
    (net (code "16") (name "INT_RTC") (class "Default")
      (node (ref "R1_PINH1") (pin "1") (pinfunction "1_1") (pintype "passive"))
      (node (ref "TP15") (pin "TP") (pinfunction "TP_TP") (pintype "input"))
      (node (ref "U2") (pin "8") (pinfunction "IO0_8") (pintype "bidirectional"))
      (node (ref "U3") (pin "3") (pinfunction "SQW/~{INT}_3") (pintype "output"))
    )
    (net (code "17") (name "IO{slash}BOOT") (class "Default")
      (node (ref "BOOT_BUTTON") (pin "3") (pinfunction "3_3") (pintype "passive"))
      (node (ref "BOOT_BUTTON") (pin "4") (pinfunction "4_4") (pintype "passive"))
      (node (ref "C6") (pin "2") (pinfunction "2_2") (pintype "passive"))
      (node (ref "R_BOOT") (pin "2") (pinfunction "2_2") (pintype "passive"))
      (node (ref "U2") (pin "15") (pinfunction "IO9_15") (pintype "bidirectional"))
    )
    (net (code "18") (name "IO{slash}CHANGE") (class "Default")
      (node (ref "C10") (pin "2") (pinfunction "2_2") (pintype "passive"))
      (node (ref "CHANGE_BUTTON") (pin "3") (pinfunction "3_3") (pintype "passive"))
      (node (ref "CHANGE_BUTTON") (pin "4") (pinfunction "4_4") (pintype "passive"))
      (node (ref "R_CHANGE") (pin "2") (pinfunction "2_2") (pintype "passive"))
      (node (ref "U2") (pin "23") (pinfunction "IO15_23") (pintype "bidirectional"))
    )
    (net (code "19") (name "MISO") (class "Default")
      (node (ref "D12") (pin "1") (pinfunction "1_1") (pintype "passive"))
      (node (ref "J4") (pin "P7") (pinfunction "DAT0_P7") (pintype "bidirectional"))
      (node (ref "R8") (pin "1") (pinfunction "1_1") (pintype "passive"))
      (node (ref "TP6") (pin "TP") (pinfunction "TP_TP") (pintype "input"))
      (node (ref "U1") (pin "2") (pinfunction "DO(IO1)_2") (pintype "bidirectional"))
      (node (ref "U2") (pin "27") (pinfunction "IO2_27") (pintype "bidirectional"))
    )
    (net (code "20") (name "MOSI") (class "Default")
      (node (ref "D11") (pin "1") (pinfunction "1_1") (pintype "passive"))
      (node (ref "J1") (pin "14") (pinfunction "14_14") (pintype "bidirectional"))
      (node (ref "J4") (pin "P3") (pinfunction "CMD_P3") (pintype "bidirectional"))
      (node (ref "R7") (pin "1") (pinfunction "1_1") (pintype "passive"))
      (node (ref "TP7") (pin "TP") (pinfunction "TP_TP") (pintype "input"))
      (node (ref "U1") (pin "5") (pinfunction "DI(IO0)_5") (pintype "bidirectional"))
      (node (ref "U2") (pin "7") (pinfunction "IO7_7") (pintype "bidirectional"))
    )
    (net (code "21") (name "Net-(CHG_LED-PadC)") (class "Default")
      (node (ref "CHG_LED") (pin "C") (pinfunction "C_C") (pintype "passive"))
      (node (ref "R1_BAT") (pin "1") (pinfunction "1_1") (pintype "passive"))
    )
    (net (code "22") (name "Net-(D2-CATHODE)") (class "Default")
      (node (ref "C1_BAT1") (pin "1") (pinfunction "1_1") (pintype "passive"))
      (node (ref "D2") (pin "1") (pinfunction "CATHODE_1") (pintype "bidirectional"))
      (node (ref "IC4") (pin "1") (pinfunction "VIN_1") (pintype "bidirectional"))
      (node (ref "IC4") (pin "3") (pinfunction "CE_3") (pintype "bidirectional"))
      (node (ref "Q1") (pin "2") (pinfunction "S_2") (pintype "bidirectional"))
    )
    (net (code "23") (name "Net-(D3-A)") (class "Default")
      (node (ref "C4") (pin "1") (pinfunction "1_1") (pintype "passive"))
      (node (ref "D3") (pin "2") (pinfunction "A_2") (pintype "bidirectional"))
      (node (ref "D4") (pin "1") (pinfunction "K_1") (pintype "bidirectional"))
    )
    (net (code "24") (name "Net-(D7-CATHODE)") (class "Default")
      (node (ref "D7") (pin "1") (pinfunction "CATHODE_1") (pintype "bidirectional"))
      (node (ref "R_CAPACITOR") (pin "2") (pinfunction "2_2") (pintype "passive"))
    )
    (net (code "25") (name "Net-(EPD_C1-Pad1)") (class "Default")
      (node (ref "EPD_C1") (pin "1") (pinfunction "1_1") (pintype "passive"))
      (node (ref "J1") (pin "4") (pinfunction "4_4") (pintype "bidirectional"))
    )
    (net (code "26") (name "Net-(EPD_C2-Pad1)") (class "Default")
      (node (ref "EPD_C2") (pin "1") (pinfunction "1_1") (pintype "passive"))
      (node (ref "J1") (pin "5") (pinfunction "5_5") (pintype "bidirectional"))
    )
    (net (code "27") (name "Net-(EPD_C6-Pad1)") (class "Default")
      (node (ref "EPD_C6") (pin "1") (pinfunction "1_1") (pintype "passive"))
      (node (ref "J1") (pin "18") (pinfunction "18_18") (pintype "bidirectional"))
    )
    (net (code "28") (name "Net-(EPD_C7-Pad1)") (class "Default")
      (node (ref "EPD_C7") (pin "1") (pinfunction "1_1") (pintype "passive"))
      (node (ref "J1") (pin "19") (pinfunction "19_19") (pintype "bidirectional"))
    )
    (net (code "29") (name "Net-(EPD_C8-Pad1)") (class "Default")
      (node (ref "EPD_C8") (pin "1") (pinfunction "1_1") (pintype "passive"))
      (node (ref "J1") (pin "20") (pinfunction "20_20") (pintype "bidirectional"))
    )
    (net (code "30") (name "Net-(EPD_C10-Pad1)") (class "Default")
      (node (ref "EPD_C10") (pin "1") (pinfunction "1_1") (pintype "passive"))
      (node (ref "J1") (pin "22") (pinfunction "22_22") (pintype "bidirectional"))
    )
    (net (code "31") (name "Net-(EPD_C12-Pad1)") (class "Default")
      (node (ref "EPD_C12") (pin "1") (pinfunction "1_1") (pintype "passive"))
      (node (ref "J1") (pin "24") (pinfunction "24_24") (pintype "bidirectional"))
    )
    (net (code "32") (name "Net-(IC1-CT)") (class "Default")
      (node (ref "C_DELAY") (pin "1") (pinfunction "1_1") (pintype "passive"))
      (node (ref "IC1") (pin "5") (pinfunction "CT_5") (pintype "bidirectional"))
    )
    (net (code "33") (name "Net-(J2-PadA5)") (class "Default")
      (node (ref "J2") (pin "A5") (pinfunction "A5_A5") (pintype "bidirectional"))
      (node (ref "R2-USB1") (pin "2") (pinfunction "2_2") (pintype "passive"))
    )
    (net (code "34") (name "Net-(J2-PadB5)") (class "Default")
      (node (ref "J2") (pin "B5") (pinfunction "B5_B5") (pintype "bidirectional"))
      (node (ref "R2-USB") (pin "1") (pinfunction "1_1") (pintype "passive"))
    )
    (net (code "35") (name "Net-(MCP73831-PROG)") (class "Default")
      (node (ref "MCP73831") (pin "5") (pinfunction "PROG_5") (pintype "input"))
      (node (ref "R2_BAT") (pin "2") (pinfunction "2_2") (pintype "passive"))
    )
    (net (code "36") (name "Net-(MCP73831-STAT)") (class "Default")
      (node (ref "MCP73831") (pin "1") (pinfunction "STAT_1") (pintype "output"))
      (node (ref "R1_BAT") (pin "2") (pinfunction "2_2") (pintype "passive"))
    )
    (net (code "37") (name "PREVGH") (class "Default")
      (node (ref "D5") (pin "1") (pinfunction "K_1") (pintype "bidirectional"))
      (node (ref "EPD_C9") (pin "1") (pinfunction "1_1") (pintype "passive"))
      (node (ref "J1") (pin "21") (pinfunction "21_21") (pintype "bidirectional"))
    )
    (net (code "38") (name "PREVGL") (class "Default")
      (node (ref "D4") (pin "2") (pinfunction "A_2") (pintype "bidirectional"))
      (node (ref "EPD_C11") (pin "1") (pinfunction "1_1") (pintype "passive"))
      (node (ref "J1") (pin "23") (pinfunction "23_23") (pintype "bidirectional"))
    )
    (net (code "39") (name "RESE") (class "Default")
      (node (ref "J1") (pin "3") (pinfunction "3_3") (pintype "bidirectional"))
      (node (ref "Q3") (pin "2") (pinfunction "S_2") (pintype "bidirectional"))
      (node (ref "R3") (pin "2") (pinfunction "2_2") (pintype "passive"))
    )
    (net (code "40") (name "RESE'") (class "Default")
      (node (ref "R2") (pin "2") (pinfunction "2_2") (pintype "passive"))
      (node (ref "R3") (pin "1") (pinfunction "1_1") (pintype "passive"))
      (node (ref "SJ1") (pin "2") (pinfunction "2_2") (pintype "passive"))
    )
    (net (code "41") (name "RESET") (class "Default")
      (node (ref "C5") (pin "1") (pinfunction "1_1") (pintype "passive"))
      (node (ref "IC1") (pin "1") (pinfunction "VOUT_1") (pintype "bidirectional"))
      (node (ref "RESET_BUTTON") (pin "3") (pinfunction "3_3") (pintype "passive"))
      (node (ref "RESET_BUTTON") (pin "4") (pinfunction "4_4") (pintype "passive"))
      (node (ref "R_RESET") (pin "2") (pinfunction "2_2") (pintype "passive"))
      (node (ref "U2") (pin "3") (pinfunction "EN_3") (pintype "input"))
    )
    (net (code "42") (name "RTC_RST") (class "Default")
      (node (ref "U2") (pin "16") (pinfunction "IO18_16") (pintype "bidirectional"))
      (node (ref "U3") (pin "4") (pinfunction "~{RST}_4") (pintype "input"))
    )
    (net (code "43") (name "RX") (class "Default")
      (node (ref "TP2") (pin "TP") (pinfunction "TP_TP") (pintype "input"))
      (node (ref "U2") (pin "24") (pinfunction "RXD0/GPIO17_24") (pintype "bidirectional"))
    )
    (net (code "44") (name "SCK") (class "Default")
      (node (ref "D10") (pin "1") (pinfunction "1_1") (pintype "passive"))
      (node (ref "J1") (pin "13") (pinfunction "13_13") (pintype "bidirectional"))
      (node (ref "J4") (pin "P5") (pinfunction "CLK_P5") (pintype "bidirectional"))
      (node (ref "R6") (pin "1") (pinfunction "1_1") (pintype "passive"))
      (node (ref "TP8") (pin "TP") (pinfunction "TP_TP") (pintype "input"))
      (node (ref "U1") (pin "6") (pinfunction "CLK_6") (pintype "input"))
      (node (ref "U2") (pin "6") (pinfunction "IO6_6") (pintype "bidirectional"))
    )
    (net (code "45") (name "SCL") (class "Default")
      (node (ref "J3") (pin "4") (pinfunction "4_4") (pintype "passive"))
      (node (ref "R2-PINH") (pin "1") (pinfunction "1_1") (pintype "passive"))
      (node (ref "SENSOR2") (pin "4") (pinfunction "SCK_4") (pintype "input"))
      (node (ref "U2") (pin "20") (pinfunction "IO22_20") (pintype "bidirectional"))
      (node (ref "U3") (pin "16") (pinfunction "SCL_16") (pintype "input"))
      (node (ref "U4") (pin "7") (pinfunction "SCL_7") (pintype "input"))
    )
    (net (code "46") (name "SDA") (class "Default")
      (node (ref "J3") (pin "3") (pinfunction "3_3") (pintype "passive"))
      (node (ref "R1_PINH") (pin "1") (pinfunction "1_1") (pintype "passive"))
      (node (ref "SENSOR2") (pin "3") (pinfunction "SDI_3") (pintype "bidirectional"))
      (node (ref "U2") (pin "19") (pinfunction "IO21_19") (pintype "bidirectional"))
      (node (ref "U3") (pin "15") (pinfunction "SDA_15") (pintype "bidirectional"))
      (node (ref "U4") (pin "8") (pinfunction "SDA_8") (pintype "bidirectional"))
    )
    (net (code "47") (name "SRC") (class "Default")
      (node (ref "C4") (pin "2") (pinfunction "2_2") (pintype "passive"))
      (node (ref "D5") (pin "2") (pinfunction "A_2") (pintype "bidirectional"))
      (node (ref "L1") (pin "1") (pinfunction "1_1") (pintype "passive"))
      (node (ref "Q3") (pin "3") (pinfunction "D_3") (pintype "bidirectional"))
    )
    (net (code "48") (name "SS_SD") (class "Default")
      (node (ref "D8") (pin "1") (pinfunction "1_1") (pintype "passive"))
      (node (ref "J4") (pin "P2") (pinfunction "CD/DAT3_P2") (pintype "bidirectional"))
      (node (ref "R10") (pin "1") (pinfunction "1_1") (pintype "passive"))
      (node (ref "U2") (pin "4") (pinfunction "IO4_4") (pintype "bidirectional"))
    )
    (net (code "49") (name "TX") (class "Default")
      (node (ref "TP1") (pin "TP") (pinfunction "TP_TP") (pintype "input"))
      (node (ref "U2") (pin "25") (pinfunction "TXD0/GPIO16_25") (pintype "bidirectional"))
    )
    (net (code "50") (name "USB_D+") (class "Default")
      (node (ref "D1") (pin "1") (pinfunction "I/O1_1_1") (pintype "bidirectional"))
      (node (ref "U2") (pin "14") (pinfunction "IO13_14") (pintype "bidirectional"))
    )
    (net (code "51") (name "USB_D-") (class "Default")
      (node (ref "D1") (pin "3") (pinfunction "I/O2_1_3") (pintype "bidirectional"))
      (node (ref "U2") (pin "13") (pinfunction "IO12_13") (pintype "bidirectional"))
    )
    (net (code "52") (name "VBAT") (class "Default")
      (node (ref "C2_BAT") (pin "1") (pinfunction "1_1") (pintype "passive"))
      (node (ref "MCP73831") (pin "3") (pinfunction "VBAT_3") (pintype "power_in"))
      (node (ref "Q1") (pin "3") (pinfunction "D_3") (pintype "bidirectional"))
      (node (ref "TP3") (pin "TP") (pinfunction "TP_TP") (pintype "input"))
      (node (ref "U4") (pin "2") (pinfunction "CELL_2") (pintype "power_in"))
      (node (ref "U4") (pin "3") (pinfunction "VDD_3") (pintype "power_in"))
    )
    (net (code "53") (name "VBUS") (class "Default")
      (node (ref "C1_BAT") (pin "1") (pinfunction "1_1") (pintype "passive"))
      (node (ref "C4_USB") (pin "1") (pinfunction "1_1") (pintype "passive"))
      (node (ref "C5_USB") (pin "1") (pinfunction "1_1") (pintype "passive"))
      (node (ref "CHG_LED") (pin "A") (pinfunction "A_A") (pintype "passive"))
      (node (ref "D1") (pin "5") (pinfunction "VBUS_5") (pintype "bidirectional"))
      (node (ref "D2") (pin "2") (pinfunction "ANODE_2") (pintype "bidirectional"))
      (node (ref "MCP73831") (pin "4") (pinfunction "VIN_4") (pintype "power_in"))
      (node (ref "PFMF.050.1") (pin "2") (pinfunction "2_2") (pintype "passive"))
      (node (ref "Q1") (pin "1") (pinfunction "G_1") (pintype "bidirectional"))
      (node (ref "R1_PWRUSB") (pin "2") (pinfunction "2_2") (pintype "passive"))
      (node (ref "TP14") (pin "TP") (pinfunction "TP_TP") (pintype "input"))
    )
    (net (code "54") (name "VRTC") (class "Default")
      (node (ref "C10_SUPERCAP") (pin "1") (pinfunction "1_1") (pintype "passive"))
      (node (ref "C8") (pin "1") (pinfunction "1_1") (pintype "passive"))
      (node (ref "R_CAPACITOR") (pin "1") (pinfunction "1_1") (pintype "passive"))
      (node (ref "U3") (pin "14") (pinfunction "VBAT_14") (pintype "power_in"))
    )
    (net (code "55") (name "VUSB") (class "Default")
      (node (ref "J2") (pin "A4") (pinfunction "A4_A4") (pintype "bidirectional"))
      (node (ref "J2") (pin "A9") (pinfunction "A9_A9") (pintype "bidirectional"))
      (node (ref "J2") (pin "B4") (pinfunction "B4_B4") (pintype "bidirectional"))
      (node (ref "J2") (pin "B9") (pinfunction "B9_B9") (pintype "bidirectional"))
      (node (ref "PFMF.050.1") (pin "1") (pinfunction "1_1") (pintype "passive"))
    )
    (net (code "56") (name "unconnected-(IC1-NC-Pad4)") (class "Default")
      (node (ref "IC1") (pin "4") (pinfunction "NC_4") (pintype "no_connect"))
    )
    (net (code "57") (name "unconnected-(IC4-NC-Pad4)") (class "Default")
      (node (ref "IC4") (pin "4") (pinfunction "NC_4") (pintype "no_connect"))
    )
    (net (code "58") (name "unconnected-(J1-Pad1)") (class "Default")
      (node (ref "J1") (pin "1") (pinfunction "1_1") (pintype "bidirectional"))
    )
    (net (code "59") (name "unconnected-(J1-Pad6)") (class "Default")
      (node (ref "J1") (pin "6") (pinfunction "6_6") (pintype "bidirectional"))
    )
    (net (code "60") (name "unconnected-(J1-Pad7)") (class "Default")
      (node (ref "J1") (pin "7") (pinfunction "7_7") (pintype "bidirectional"))
    )
    (net (code "61") (name "unconnected-(J2-PadA8)") (class "Default")
      (node (ref "J2") (pin "A8") (pinfunction "A8_A8") (pintype "bidirectional"))
    )
    (net (code "62") (name "unconnected-(J2-PadB8)") (class "Default")
      (node (ref "J2") (pin "B8") (pinfunction "B8_B8") (pintype "bidirectional"))
    )
    (net (code "63") (name "unconnected-(J4-DAT1-PadP8)") (class "Default")
      (node (ref "J4") (pin "P8") (pinfunction "DAT1_P8") (pintype "bidirectional"))
    )
    (net (code "64") (name "unconnected-(J4-DAT2-PadP1)") (class "Default")
      (node (ref "J4") (pin "P1") (pinfunction "DAT2_P1") (pintype "bidirectional"))
    )
    (net (code "65") (name "unconnected-(J4-DETECTION_1-PadS1)") (class "Default")
      (node (ref "J4") (pin "S1") (pinfunction "DETECTION_1_S1") (pintype "bidirectional"))
    )
    (net (code "66") (name "unconnected-(J4-DETECTION_2-PadS2)") (class "Default")
      (node (ref "J4") (pin "S2") (pinfunction "DETECTION_2_S2") (pintype "bidirectional"))
    )
    (net (code "67") (name "unconnected-(U2-NC-Pad22)") (class "Default")
      (node (ref "U2") (pin "22") (pinfunction "NC_22") (pintype "no_connect"))
    )
    (net (code "68") (name "unconnected-(U4-~{ALERT}-Pad5)") (class "Default")
      (node (ref "U4") (pin "5") (pinfunction "~{ALERT}_5") (pintype "output"))
    )
  )
)
